# GarageDoor.net
KiCad netlist of a schematic drawn in EAGLE
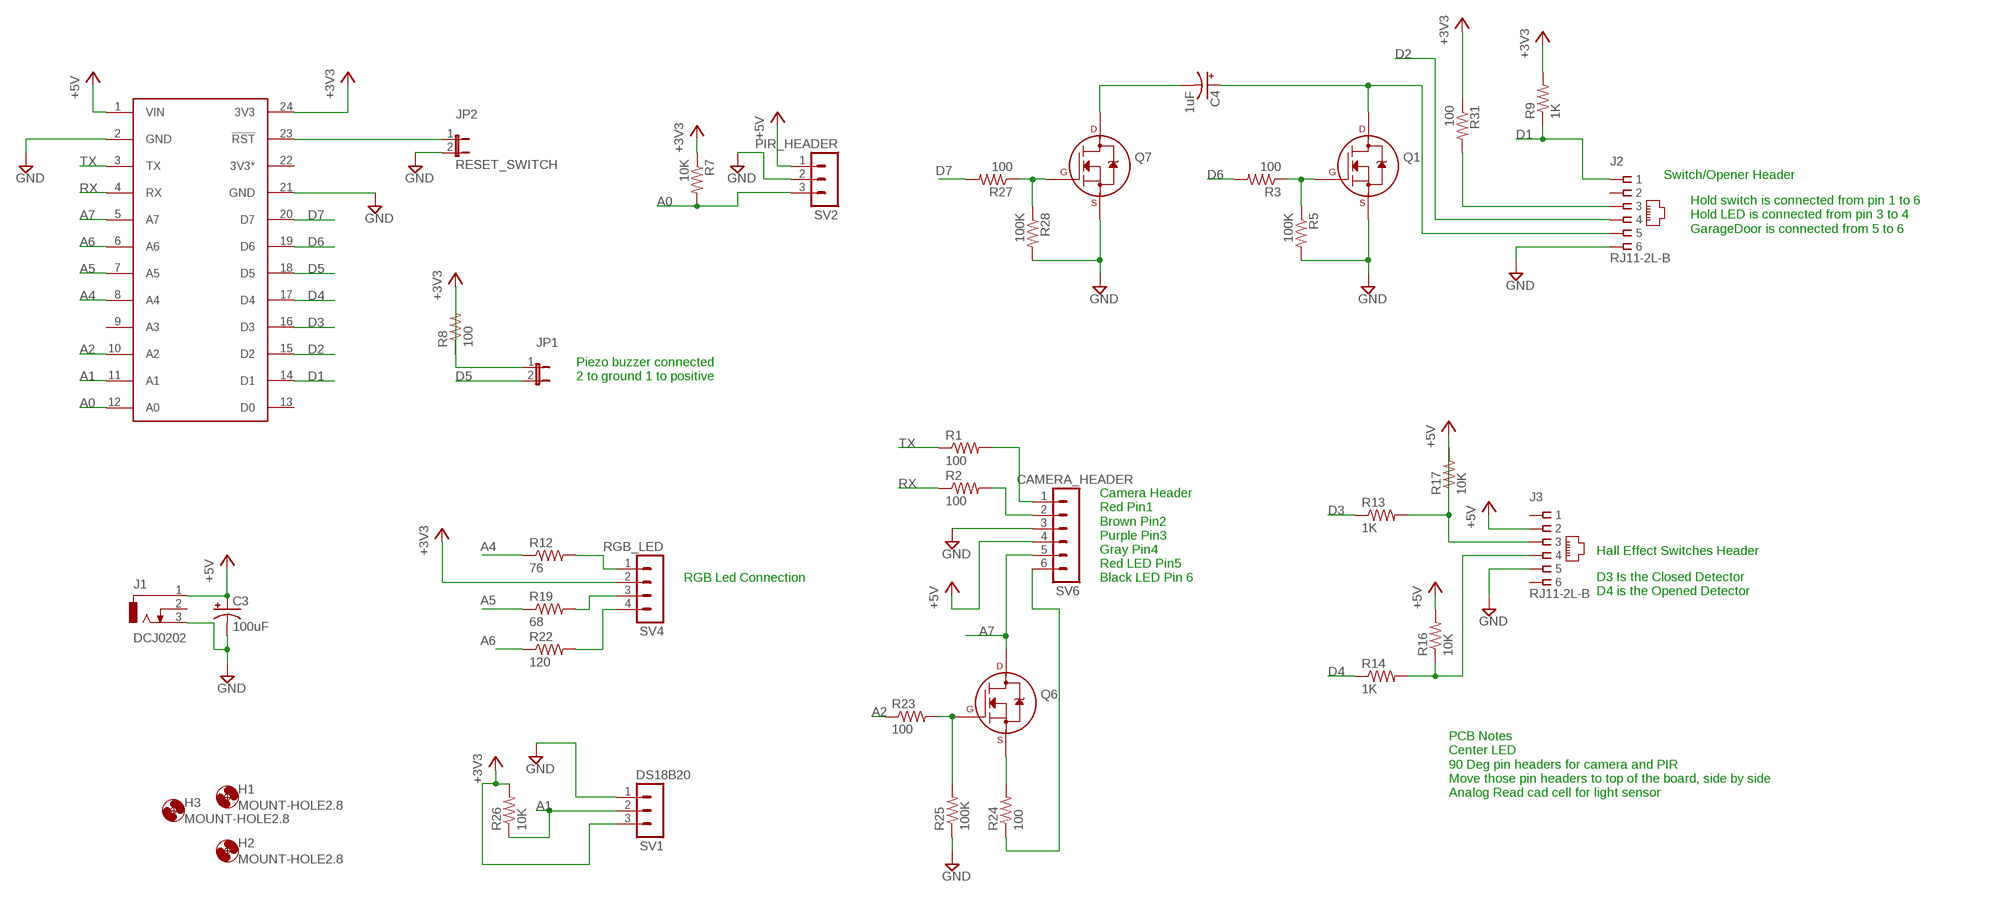
[diagram p0: schematic, sheet 1]

(export (version "E")
  (design (tool "Eeschema 10.0.6"))
  (components
    (comp (ref "C3")
      (value "100uF")
      (footprint "eagle-import:E2,5-6E")
      (libsource (lib "eagle-import") (part "CPOL-USE2,5-6E"))
    )
    (comp (ref "C4")
      (value "1uF")
      (footprint "eagle-import:E2,5-6E")
      (libsource (lib "eagle-import") (part "CPOL-USE2,5-6E"))
    )
    (comp (ref "H1")
      (value "MOUNT-HOLE2.8")
      (footprint "eagle-import:2,8")
      (libsource (lib "eagle-import") (part "MOUNT-HOLE2.8"))
    )
    (comp (ref "H2")
      (value "MOUNT-HOLE2.8")
      (footprint "eagle-import:2,8")
      (libsource (lib "eagle-import") (part "MOUNT-HOLE2.8"))
    )
    (comp (ref "H3")
      (value "MOUNT-HOLE2.8")
      (footprint "eagle-import:2,8")
      (libsource (lib "eagle-import") (part "MOUNT-HOLE2.8"))
    )
    (comp (ref "J1")
      (value "DCJ0202")
      (footprint "eagle-import:DCJ0202")
      (libsource (lib "eagle-import") (part "DCJ0202"))
    )
    (comp (ref "J2")
      (value "RJ11-2L-B")
      (footprint "eagle-import:RJ11-NO_SHIELD")
      (fields (field (name "MF") "TYCO ELECTRONICS"))
      (libsource (lib "eagle-import") (part "RJ11-2L-B"))
    )
    (comp (ref "J3")
      (value "RJ11-2L-B")
      (footprint "eagle-import:RJ11-NO_SHIELD")
      (fields (field (name "MF") "TYCO ELECTRONICS"))
      (libsource (lib "eagle-import") (part "RJ11-2L-B"))
    )
    (comp (ref "JP1")
      (value "JP1E")
      (footprint "eagle-import:JP1")
      (libsource (lib "eagle-import") (part "JP1E"))
    )
    (comp (ref "JP2")
      (value "RESET_SWITCH")
      (footprint "eagle-import:JP1")
      (libsource (lib "eagle-import") (part "JP1E"))
    )
    (comp (ref "Q1")
      (value "2N7000_SOT23")
      (footprint "eagle-import:SOT-23")
      (libsource (lib "eagle-import") (part "2N700_SOT230"))
    )
    (comp (ref "Q6")
      (value "2N7000_SOT23")
      (footprint "eagle-import:SOT-23")
      (libsource (lib "eagle-import") (part "2N700_SOT230"))
    )
    (comp (ref "Q7")
      (value "2N7000_SOT23")
      (footprint "eagle-import:SOT-23")
      (libsource (lib "eagle-import") (part "2N700_SOT230"))
    )
    (comp (ref "R1")
      (value "100")
      (footprint "eagle-import:R0805")
      (libsource (lib "eagle-import") (part "R-US_R0805"))
    )
    (comp (ref "R2")
      (value "100")
      (footprint "eagle-import:R0805")
      (libsource (lib "eagle-import") (part "R-US_R0805"))
    )
    (comp (ref "R3")
      (value "100")
      (footprint "eagle-import:R0805")
      (libsource (lib "eagle-import") (part "R-US_R0805"))
    )
    (comp (ref "R5")
      (value "100K")
      (footprint "eagle-import:R0805")
      (libsource (lib "eagle-import") (part "R-US_R0805"))
    )
    (comp (ref "R7")
      (value "10K")
      (footprint "eagle-import:R0805")
      (libsource (lib "eagle-import") (part "R-US_R0805"))
    )
    (comp (ref "R8")
      (value "100")
      (footprint "eagle-import:R0805")
      (libsource (lib "eagle-import") (part "R-US_R0805"))
    )
    (comp (ref "R9")
      (value "1K")
      (footprint "eagle-import:R0805")
      (libsource (lib "eagle-import") (part "R-US_R0805"))
    )
    (comp (ref "R12")
      (value "76")
      (footprint "eagle-import:R0805")
      (libsource (lib "eagle-import") (part "R-US_R0805"))
    )
    (comp (ref "R13")
      (value "1K")
      (footprint "eagle-import:R0805")
      (libsource (lib "eagle-import") (part "R-US_R0805"))
    )
    (comp (ref "R14")
      (value "1K")
      (footprint "eagle-import:R0805")
      (libsource (lib "eagle-import") (part "R-US_R0805"))
    )
    (comp (ref "R16")
      (value "10K")
      (footprint "eagle-import:R0805")
      (libsource (lib "eagle-import") (part "R-US_R0805"))
    )
    (comp (ref "R17")
      (value "10K")
      (footprint "eagle-import:R0805")
      (libsource (lib "eagle-import") (part "R-US_R0805"))
    )
    (comp (ref "R19")
      (value "68")
      (footprint "eagle-import:R0805")
      (libsource (lib "eagle-import") (part "R-US_R0805"))
    )
    (comp (ref "R22")
      (value "120")
      (footprint "eagle-import:R0805")
      (libsource (lib "eagle-import") (part "R-US_R0805"))
    )
    (comp (ref "R23")
      (value "100")
      (footprint "eagle-import:R0805")
      (libsource (lib "eagle-import") (part "R-US_R0805"))
    )
    (comp (ref "R24")
      (value "100")
      (footprint "eagle-import:R0805")
      (libsource (lib "eagle-import") (part "R-US_R0805"))
    )
    (comp (ref "R25")
      (value "100K")
      (footprint "eagle-import:R0805")
      (libsource (lib "eagle-import") (part "R-US_R0805"))
    )
    (comp (ref "R26")
      (value "10K")
      (footprint "eagle-import:R0805")
      (libsource (lib "eagle-import") (part "R-US_R0805"))
    )
    (comp (ref "R27")
      (value "100")
      (footprint "eagle-import:R0805")
      (libsource (lib "eagle-import") (part "R-US_R0805"))
    )
    (comp (ref "R28")
      (value "100K")
      (footprint "eagle-import:R0805")
      (libsource (lib "eagle-import") (part "R-US_R0805"))
    )
    (comp (ref "R31")
      (value "100")
      (footprint "eagle-import:R0805")
      (libsource (lib "eagle-import") (part "R-US_R0805"))
    )
    (comp (ref "SC1")
      (value "SPARK_CORECORE")
      (footprint "eagle-import:SPARK_CORE")
      (libsource (lib "eagle-import") (part "SPARK_CORECORE"))
    )
    (comp (ref "SV1")
      (value "DS18B20")
      (footprint "eagle-import:MA03-1")
      (libsource (lib "eagle-import") (part "MA03-1"))
    )
    (comp (ref "SV2")
      (value "PIR_HEADER")
      (footprint "eagle-import:MA03-1")
      (libsource (lib "eagle-import") (part "MA03-1"))
    )
    (comp (ref "SV4")
      (value "RGB_LED")
      (footprint "eagle-import:MA04-1")
      (libsource (lib "eagle-import") (part "MA04-1"))
    )
    (comp (ref "SV6")
      (value "CAMERA_HEADER")
      (footprint "eagle-import:MA06-1")
      (libsource (lib "eagle-import") (part "MA06-1"))
    )
  )
  (nets
    (net (code "1") (name "+3V3") (class "Default")
      (node (ref "R26") (pin "2") (pinfunction "2_2") (pintype "passive"))
      (node (ref "R31") (pin "1") (pinfunction "1_1") (pintype "passive"))
      (node (ref "R7") (pin "1") (pinfunction "1_1") (pintype "passive"))
      (node (ref "R8") (pin "1") (pinfunction "1_1") (pintype "passive"))
      (node (ref "R9") (pin "2") (pinfunction "2_2") (pintype "passive"))
      (node (ref "SC1") (pin "24") (pinfunction "3V3_24") (pintype "power_in"))
      (node (ref "SV1") (pin "3") (pinfunction "3_3") (pintype "passive"))
      (node (ref "SV4") (pin "2") (pinfunction "2_2") (pintype "passive"))
    )
    (net (code "2") (name "+5V") (class "Default")
      (node (ref "C3") (pin "+") (pinfunction "+_+") (pintype "passive"))
      (node (ref "J1") (pin "1") (pinfunction "1_1") (pintype "passive"))
      (node (ref "J3") (pin "2") (pinfunction "2_2") (pintype "passive"))
      (node (ref "R16") (pin "2") (pinfunction "2_2") (pintype "passive"))
      (node (ref "R17") (pin "1") (pinfunction "1_1") (pintype "passive"))
      (node (ref "SC1") (pin "1") (pinfunction "VIN_1") (pintype "power_in"))
      (node (ref "SV2") (pin "1") (pinfunction "1_1") (pintype "passive"))
      (node (ref "SV6") (pin "4") (pinfunction "4_4") (pintype "passive"))
    )
    (net (code "3") (name "/3V3*") (class "Default")
      (node (ref "SC1") (pin "22") (pinfunction "3V3*_22") (pintype "power_in"))
    )
    (net (code "4") (name "/A0") (class "Default")
      (node (ref "R7") (pin "2") (pinfunction "2_2") (pintype "passive"))
      (node (ref "SC1") (pin "12") (pinfunction "A0_12") (pintype "bidirectional"))
      (node (ref "SV2") (pin "3") (pinfunction "3_3") (pintype "passive"))
    )
    (net (code "5") (name "/A1") (class "Default")
      (node (ref "R26") (pin "1") (pinfunction "1_1") (pintype "passive"))
      (node (ref "SC1") (pin "11") (pinfunction "A1_11") (pintype "bidirectional"))
      (node (ref "SV1") (pin "2") (pinfunction "2_2") (pintype "passive"))
    )
    (net (code "6") (name "/A2") (class "Default")
      (node (ref "R23") (pin "1") (pinfunction "1_1") (pintype "passive"))
      (node (ref "SC1") (pin "10") (pinfunction "A2_10") (pintype "bidirectional"))
    )
    (net (code "7") (name "/A4") (class "Default")
      (node (ref "R12") (pin "1") (pinfunction "1_1") (pintype "passive"))
      (node (ref "SC1") (pin "8") (pinfunction "A4_8") (pintype "bidirectional"))
    )
    (net (code "8") (name "/A5") (class "Default")
      (node (ref "R19") (pin "1") (pinfunction "1_1") (pintype "passive"))
      (node (ref "SC1") (pin "7") (pinfunction "A5_7") (pintype "bidirectional"))
    )
    (net (code "9") (name "/A6") (class "Default")
      (node (ref "R22") (pin "1") (pinfunction "1_1") (pintype "passive"))
      (node (ref "SC1") (pin "6") (pinfunction "A6_6") (pintype "bidirectional"))
    )
    (net (code "10") (name "/A7") (class "Default")
      (node (ref "Q6") (pin "3") (pinfunction "D_3") (pintype "bidirectional"))
      (node (ref "SC1") (pin "5") (pinfunction "A7_5") (pintype "bidirectional"))
      (node (ref "SV6") (pin "5") (pinfunction "5_5") (pintype "passive"))
    )
    (net (code "11") (name "/D1") (class "Default")
      (node (ref "J2") (pin "1") (pinfunction "1_1") (pintype "passive"))
      (node (ref "R9") (pin "1") (pinfunction "1_1") (pintype "passive"))
      (node (ref "SC1") (pin "14") (pinfunction "D1_14") (pintype "bidirectional"))
    )
    (net (code "12") (name "/D2") (class "Default")
      (node (ref "J2") (pin "4") (pinfunction "4_4") (pintype "passive"))
      (node (ref "SC1") (pin "15") (pinfunction "D2_15") (pintype "bidirectional"))
    )
    (net (code "13") (name "/D3") (class "Default")
      (node (ref "R13") (pin "1") (pinfunction "1_1") (pintype "passive"))
      (node (ref "SC1") (pin "16") (pinfunction "D3_16") (pintype "bidirectional"))
    )
    (net (code "14") (name "/D4") (class "Default")
      (node (ref "R14") (pin "1") (pinfunction "1_1") (pintype "passive"))
      (node (ref "SC1") (pin "17") (pinfunction "D4_17") (pintype "bidirectional"))
    )
    (net (code "15") (name "/D5") (class "Default")
      (node (ref "JP1") (pin "2") (pinfunction "2_2") (pintype "passive"))
      (node (ref "SC1") (pin "18") (pinfunction "D5_18") (pintype "bidirectional"))
    )
    (net (code "16") (name "/D6") (class "Default")
      (node (ref "R3") (pin "2") (pinfunction "2_2") (pintype "passive"))
      (node (ref "SC1") (pin "19") (pinfunction "D6_19") (pintype "bidirectional"))
    )
    (net (code "17") (name "/D7") (class "Default")
      (node (ref "R27") (pin "2") (pinfunction "2_2") (pintype "passive"))
      (node (ref "SC1") (pin "20") (pinfunction "D7_20") (pintype "bidirectional"))
    )
    (net (code "18") (name "/RX") (class "Default")
      (node (ref "R2") (pin "1") (pinfunction "1_1") (pintype "passive"))
      (node (ref "SC1") (pin "4") (pinfunction "RX_4") (pintype "bidirectional"))
    )
    (net (code "19") (name "/TX") (class "Default")
      (node (ref "R1") (pin "1") (pinfunction "1_1") (pintype "passive"))
      (node (ref "SC1") (pin "3") (pinfunction "TX_3") (pintype "bidirectional"))
    )
    (net (code "20") (name "GND") (class "Default")
      (node (ref "C3") (pin "-") (pinfunction "-_-") (pintype "passive"))
      (node (ref "J1") (pin "3") (pinfunction "3_3") (pintype "passive"))
      (node (ref "J2") (pin "6") (pinfunction "6_6") (pintype "passive"))
      (node (ref "J3") (pin "5") (pinfunction "5_5") (pintype "passive"))
      (node (ref "JP2") (pin "2") (pinfunction "2_2") (pintype "passive"))
      (node (ref "Q1") (pin "2") (pinfunction "S_2") (pintype "bidirectional"))
      (node (ref "Q7") (pin "2") (pinfunction "S_2") (pintype "bidirectional"))
      (node (ref "R25") (pin "1") (pinfunction "1_1") (pintype "passive"))
      (node (ref "R28") (pin "2") (pinfunction "2_2") (pintype "passive"))
      (node (ref "R5") (pin "2") (pinfunction "2_2") (pintype "passive"))
      (node (ref "SC1") (pin "2") (pinfunction "GND_2") (pintype "power_in"))
      (node (ref "SC1") (pin "21") (pinfunction "GND_21") (pintype "power_in"))
      (node (ref "SV1") (pin "1") (pinfunction "1_1") (pintype "passive"))
      (node (ref "SV2") (pin "2") (pinfunction "2_2") (pintype "passive"))
      (node (ref "SV6") (pin "3") (pinfunction "3_3") (pintype "passive"))
    )
    (net (code "21") (name "Net-(J2-Pad3)") (class "Default")
      (node (ref "J2") (pin "3") (pinfunction "3_3") (pintype "passive"))
      (node (ref "R31") (pin "2") (pinfunction "2_2") (pintype "passive"))
    )
    (net (code "22") (name "Net-(J3-Pad3)") (class "Default")
      (node (ref "J3") (pin "3") (pinfunction "3_3") (pintype "passive"))
      (node (ref "R13") (pin "2") (pinfunction "2_2") (pintype "passive"))
      (node (ref "R17") (pin "2") (pinfunction "2_2") (pintype "passive"))
    )
    (net (code "23") (name "Net-(J3-Pad4)") (class "Default")
      (node (ref "J3") (pin "4") (pinfunction "4_4") (pintype "passive"))
      (node (ref "R14") (pin "2") (pinfunction "2_2") (pintype "passive"))
      (node (ref "R16") (pin "1") (pinfunction "1_1") (pintype "passive"))
    )
    (net (code "24") (name "Net-(JP1-Pad1)") (class "Default")
      (node (ref "JP1") (pin "1") (pinfunction "1_1") (pintype "passive"))
      (node (ref "R8") (pin "2") (pinfunction "2_2") (pintype "passive"))
    )
    (net (code "25") (name "Net-(Q1-D)") (class "Default")
      (node (ref "C4") (pin "+") (pinfunction "+_+") (pintype "passive"))
      (node (ref "J2") (pin "5") (pinfunction "5_5") (pintype "passive"))
      (node (ref "Q1") (pin "3") (pinfunction "D_3") (pintype "bidirectional"))
    )
    (net (code "26") (name "Net-(Q1-G)") (class "Default")
      (node (ref "Q1") (pin "1") (pinfunction "G_1") (pintype "tri_state"))
      (node (ref "R3") (pin "1") (pinfunction "1_1") (pintype "passive"))
      (node (ref "R5") (pin "1") (pinfunction "1_1") (pintype "passive"))
    )
    (net (code "27") (name "Net-(Q6-G)") (class "Default")
      (node (ref "Q6") (pin "1") (pinfunction "G_1") (pintype "tri_state"))
      (node (ref "R23") (pin "2") (pinfunction "2_2") (pintype "passive"))
      (node (ref "R25") (pin "2") (pinfunction "2_2") (pintype "passive"))
    )
    (net (code "28") (name "Net-(Q6-S)") (class "Default")
      (node (ref "Q6") (pin "2") (pinfunction "S_2") (pintype "bidirectional"))
      (node (ref "R24") (pin "2") (pinfunction "2_2") (pintype "passive"))
    )
    (net (code "29") (name "Net-(Q7-D)") (class "Default")
      (node (ref "C4") (pin "-") (pinfunction "-_-") (pintype "passive"))
      (node (ref "Q7") (pin "3") (pinfunction "D_3") (pintype "bidirectional"))
    )
    (net (code "30") (name "Net-(Q7-G)") (class "Default")
      (node (ref "Q7") (pin "1") (pinfunction "G_1") (pintype "tri_state"))
      (node (ref "R27") (pin "1") (pinfunction "1_1") (pintype "passive"))
      (node (ref "R28") (pin "1") (pinfunction "1_1") (pintype "passive"))
    )
    (net (code "31") (name "Net-(R1-Pad2)") (class "Default")
      (node (ref "R1") (pin "2") (pinfunction "2_2") (pintype "passive"))
      (node (ref "SV6") (pin "1") (pinfunction "1_1") (pintype "passive"))
    )
    (net (code "32") (name "Net-(R2-Pad2)") (class "Default")
      (node (ref "R2") (pin "2") (pinfunction "2_2") (pintype "passive"))
      (node (ref "SV6") (pin "2") (pinfunction "2_2") (pintype "passive"))
    )
    (net (code "33") (name "Net-(R12-Pad2)") (class "Default")
      (node (ref "R12") (pin "2") (pinfunction "2_2") (pintype "passive"))
      (node (ref "SV4") (pin "1") (pinfunction "1_1") (pintype "passive"))
    )
    (net (code "34") (name "Net-(R19-Pad2)") (class "Default")
      (node (ref "R19") (pin "2") (pinfunction "2_2") (pintype "passive"))
      (node (ref "SV4") (pin "3") (pinfunction "3_3") (pintype "passive"))
    )
    (net (code "35") (name "Net-(R22-Pad2)") (class "Default")
      (node (ref "R22") (pin "2") (pinfunction "2_2") (pintype "passive"))
      (node (ref "SV4") (pin "4") (pinfunction "4_4") (pintype "passive"))
    )
    (net (code "36") (name "Net-(R24-Pad1)") (class "Default")
      (node (ref "R24") (pin "1") (pinfunction "1_1") (pintype "passive"))
      (node (ref "SV6") (pin "6") (pinfunction "6_6") (pintype "passive"))
    )
    (net (code "37") (name "Net-(SC1-~{RST})") (class "Default")
      (node (ref "JP2") (pin "1") (pinfunction "1_1") (pintype "passive"))
      (node (ref "SC1") (pin "23") (pinfunction "~{RST}_23") (pintype "bidirectional"))
    )
    (net (code "38") (name "unconnected-(J1-Pad2)") (class "Default")
      (node (ref "J1") (pin "2") (pinfunction "2_2") (pintype "passive"))
    )
    (net (code "39") (name "unconnected-(J2-Pad2)") (class "Default")
      (node (ref "J2") (pin "2") (pinfunction "2_2") (pintype "passive"))
    )
    (net (code "40") (name "unconnected-(J3-Pad1)") (class "Default")
      (node (ref "J3") (pin "1") (pinfunction "1_1") (pintype "passive"))
    )
    (net (code "41") (name "unconnected-(J3-Pad6)") (class "Default")
      (node (ref "J3") (pin "6") (pinfunction "6_6") (pintype "passive"))
    )
    (net (code "42") (name "unconnected-(SC1-A3-Pad9)") (class "Default")
      (node (ref "SC1") (pin "9") (pinfunction "A3_9") (pintype "bidirectional"))
    )
    (net (code "43") (name "unconnected-(SC1-D0-Pad13)") (class "Default")
      (node (ref "SC1") (pin "13") (pinfunction "D0_13") (pintype "bidirectional"))
    )
  )
)
